# SCH_usbc_module_2022-02-18.net
KiCad netlist of a schematic drawn in EasyEDA
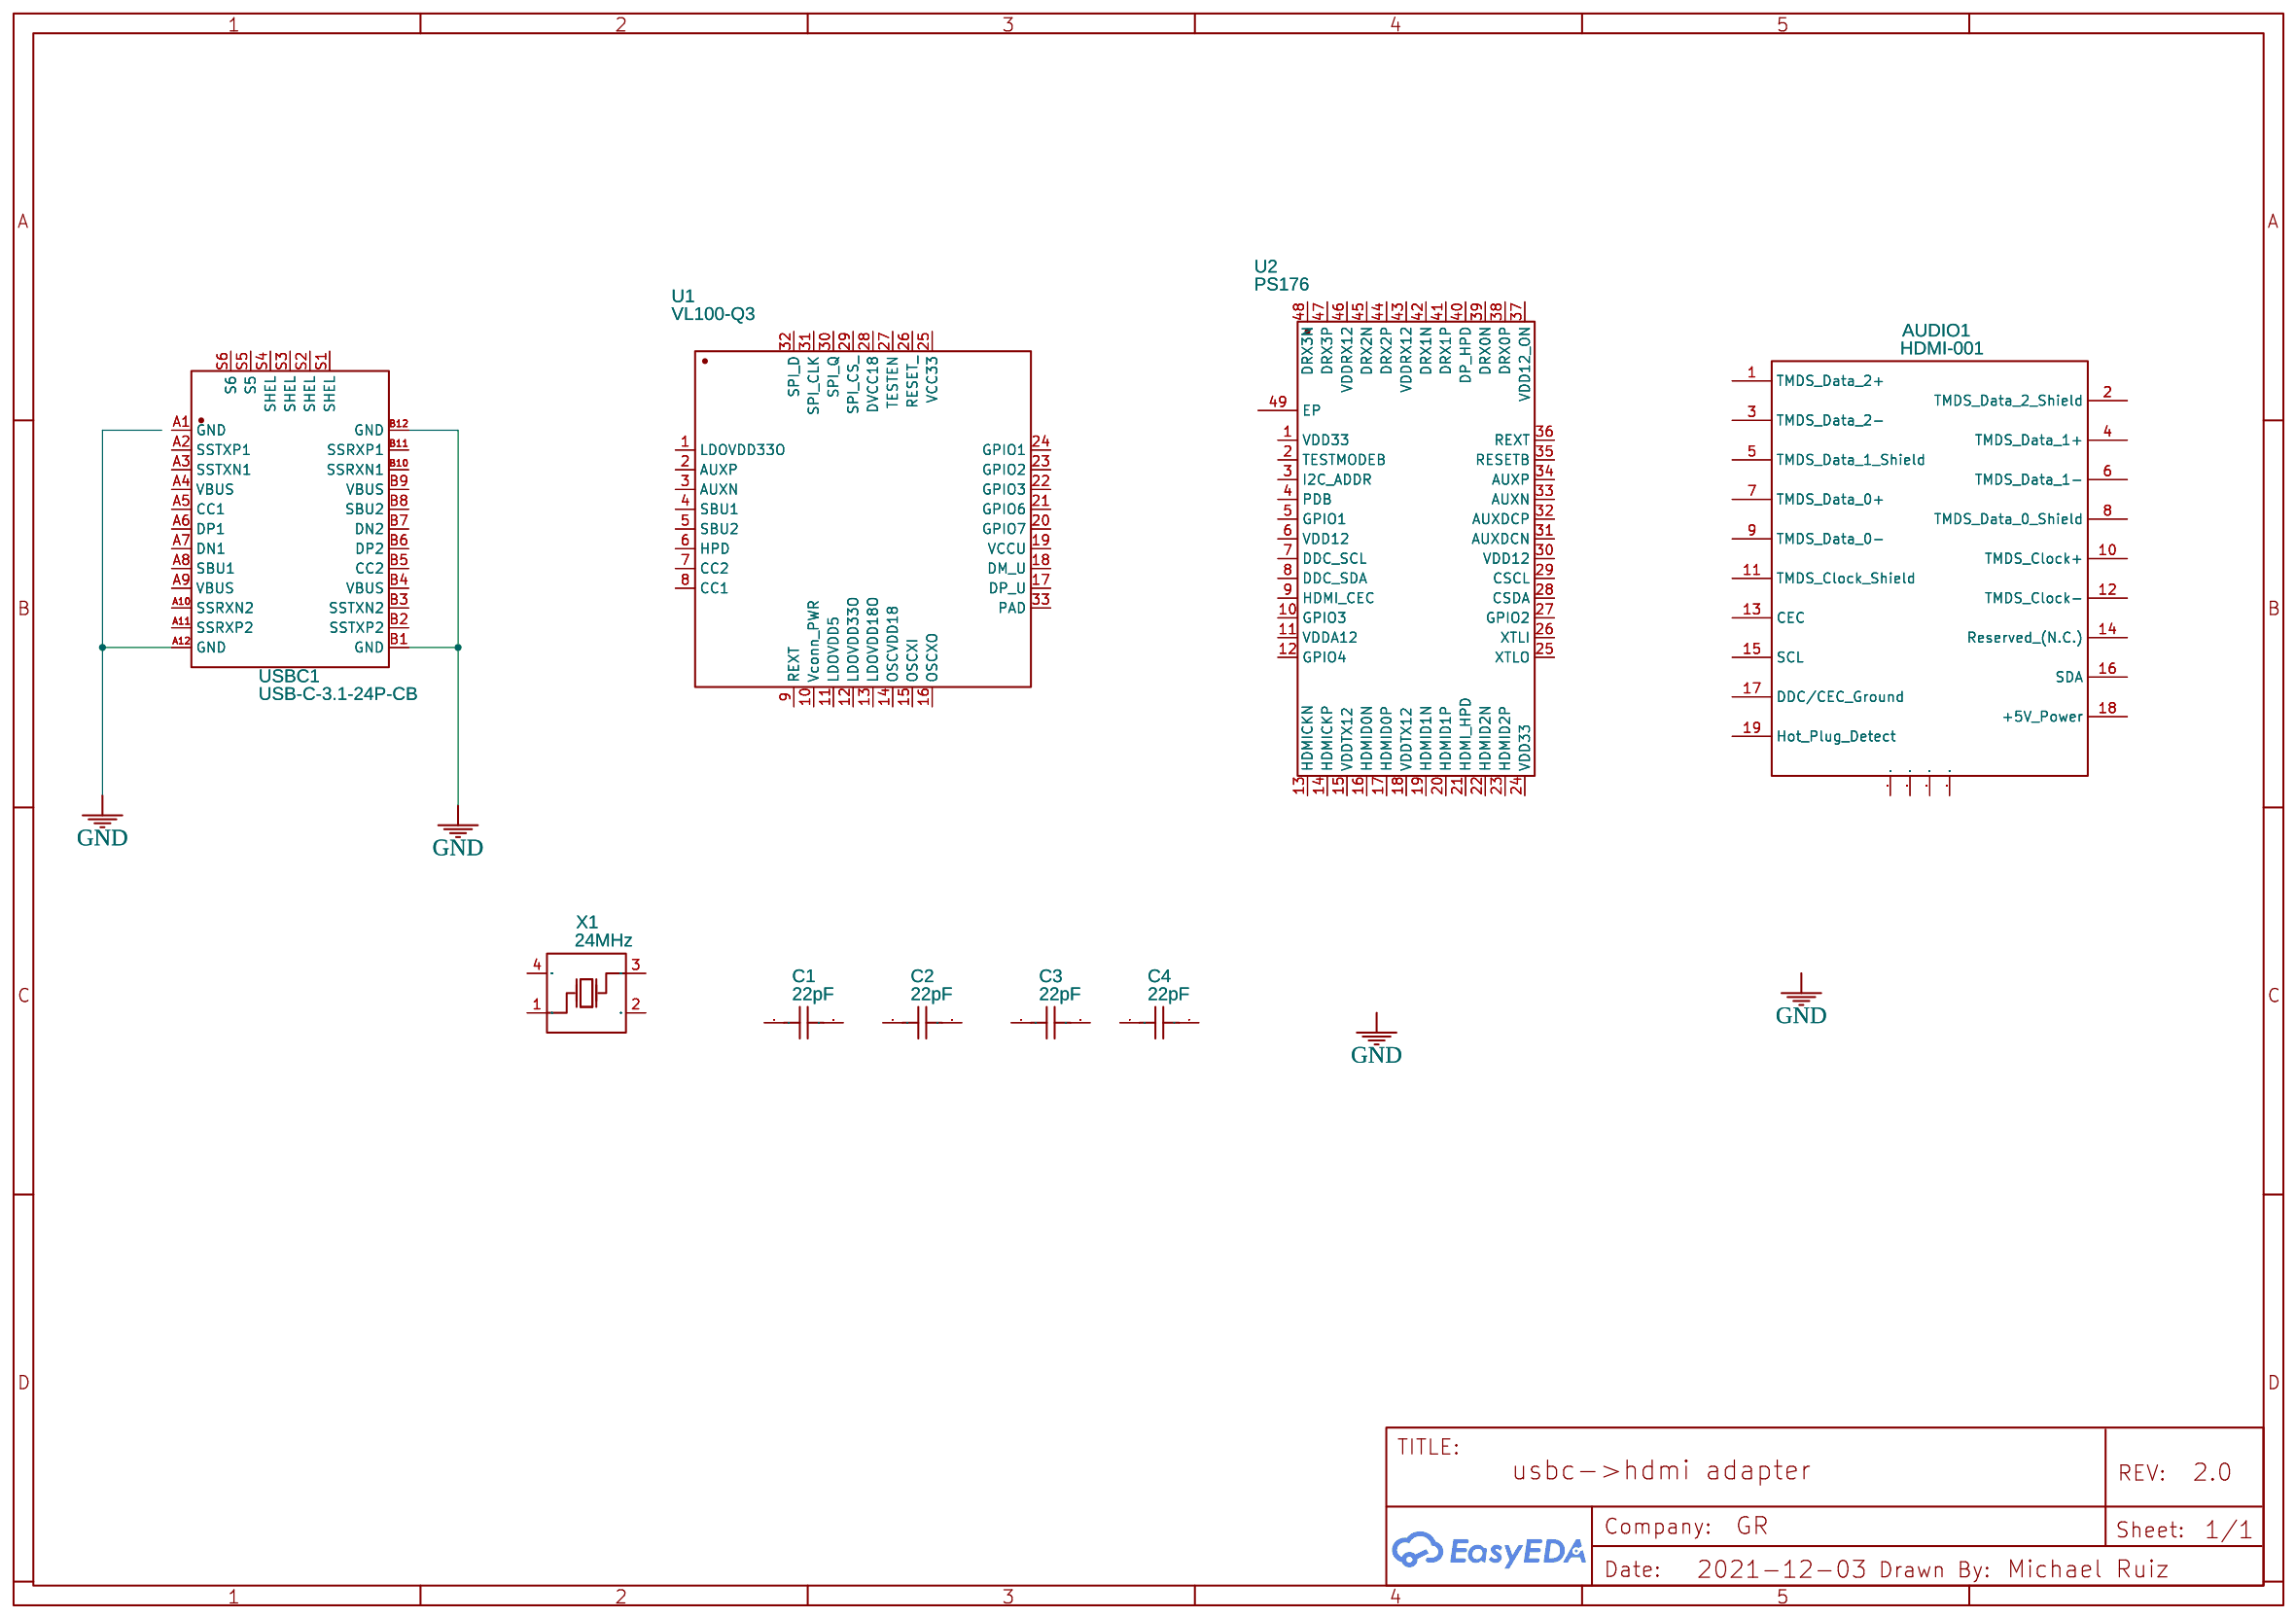
[diagram p0: schematic sheet]

(export (version "E")
  (design (tool "Eeschema 10.0.6"))
  (components
    (comp (ref "AUDIO1")
      (value "HDMI-001")
      (fields (field (name "BOM_Supplier Part") "C138388"))
      (libsource (lib "") (part "HDMI-001"))
    )
    (comp (ref "C1")
      (value "22pF")
      (fields
        (field (name "BOM_Manufacturer Part") "0603N220J500CT")
        (field (name "BOM_Supplier Part") "C2875465")
      )
      (libsource (lib "") (part "0603N220J500CT_C2875465"))
    )
    (comp (ref "C2")
      (value "22pF")
      (fields
        (field (name "BOM_Manufacturer Part") "0603N220J500CT")
        (field (name "BOM_Supplier Part") "C2875465")
      )
      (libsource (lib "") (part "0603N220J500CT_C2875465"))
    )
    (comp (ref "C3")
      (value "22pF")
      (fields
        (field (name "BOM_Manufacturer Part") "0603N220J500CT")
        (field (name "BOM_Supplier Part") "C2875465")
      )
      (libsource (lib "") (part "0603N220J500CT_C2875465"))
    )
    (comp (ref "C4")
      (value "22pF")
      (fields
        (field (name "BOM_Manufacturer Part") "0603N220J500CT")
        (field (name "BOM_Supplier Part") "C2875465")
      )
      (libsource (lib "") (part "0603N220J500CT_C2875465"))
    )
    (comp (ref "U1")
      (value "VL100-Q3")
      (fields (field (name "BOM_Supplier Part") "C69731"))
      (libsource (lib "") (part "VL100-Q3"))
    )
    (comp (ref "U2")
      (value "PS176")
      (fields (field (name "BOM_Supplier Part") "C209703"))
      (libsource (lib "") (part "PS176"))
    )
    (comp (ref "USBC1")
      (value "USB-C-3.1-24P-CB")
      (fields (field (name "BOM_Supplier Part") "C67379"))
      (libsource (lib "") (part "USB-C-3.1-24P-CB"))
    )
    (comp (ref "X1")
      (value "24MHz")
      (fields
        (field (name "BOM_Manufacturer Part") "S2224000091060")
        (field (name "BOM_Supplier Part") "C479185")
      )
      (libsource (lib "") (part "S2224000091060"))
    )
  )
  (nets
    (net (code "1") (name "GND") (class "Default")
      (node (ref "USBC1") (pin "A12") (pinfunction "GND_A12") (pintype "unspecified"))
      (node (ref "USBC1") (pin "B1") (pinfunction "GND_B1") (pintype "unspecified"))
      (node (ref "USBC1") (pin "B12") (pinfunction "GND_B12") (pintype "unspecified"))
    )
    (net (code "2") (name "unconnected-(AUDIO1-+5V_Power-Pad18)") (class "Default")
      (node (ref "AUDIO1") (pin "18") (pinfunction "+5V_Power_18") (pintype "unspecified"))
    )
    (net (code "3") (name "unconnected-(AUDIO1-CEC-Pad13)") (class "Default")
      (node (ref "AUDIO1") (pin "13") (pinfunction "CEC_13") (pintype "unspecified"))
    )
    (net (code "4") (name "unconnected-(AUDIO1-DDC{slash}CEC_Ground-Pad17)") (class "Default")
      (node (ref "AUDIO1") (pin "17") (pinfunction "DDC/CEC_Ground_17") (pintype "unspecified"))
    )
    (net (code "5") (name "unconnected-(AUDIO1-Hot_Plug_Detect-Pad19)") (class "Default")
      (node (ref "AUDIO1") (pin "19") (pinfunction "Hot_Plug_Detect_19") (pintype "unspecified"))
    )
    (net (code "6") (name "unconnected-(AUDIO1-Pad20)") (class "Default")
      (node (ref "AUDIO1") (pin "20") (pinfunction "20_20") (pintype "unspecified"))
    )
    (net (code "7") (name "unconnected-(AUDIO1-Pad21)") (class "Default")
      (node (ref "AUDIO1") (pin "21") (pinfunction "21_21") (pintype "unspecified"))
    )
    (net (code "8") (name "unconnected-(AUDIO1-Pad22)") (class "Default")
      (node (ref "AUDIO1") (pin "22") (pinfunction "22_22") (pintype "unspecified"))
    )
    (net (code "9") (name "unconnected-(AUDIO1-Pad23)") (class "Default")
      (node (ref "AUDIO1") (pin "23") (pinfunction "23_23") (pintype "unspecified"))
    )
    (net (code "10") (name "unconnected-(AUDIO1-Reserved_(N.C.)-Pad14)") (class "Default")
      (node (ref "AUDIO1") (pin "14") (pinfunction "Reserved_(N.C.)_14") (pintype "unspecified"))
    )
    (net (code "11") (name "unconnected-(AUDIO1-SCL-Pad15)") (class "Default")
      (node (ref "AUDIO1") (pin "15") (pinfunction "SCL_15") (pintype "unspecified"))
    )
    (net (code "12") (name "unconnected-(AUDIO1-SDA-Pad16)") (class "Default")
      (node (ref "AUDIO1") (pin "16") (pinfunction "SDA_16") (pintype "unspecified"))
    )
    (net (code "13") (name "unconnected-(AUDIO1-TMDS_Clock+-Pad10)") (class "Default")
      (node (ref "AUDIO1") (pin "10") (pinfunction "TMDS_Clock+_10") (pintype "unspecified"))
    )
    (net (code "14") (name "unconnected-(AUDIO1-TMDS_Clock--Pad12)") (class "Default")
      (node (ref "AUDIO1") (pin "12") (pinfunction "TMDS_Clock-_12") (pintype "unspecified"))
    )
    (net (code "15") (name "unconnected-(AUDIO1-TMDS_Clock_Shield-Pad11)") (class "Default")
      (node (ref "AUDIO1") (pin "11") (pinfunction "TMDS_Clock_Shield_11") (pintype "unspecified"))
    )
    (net (code "16") (name "unconnected-(AUDIO1-TMDS_Data_0+-Pad7)") (class "Default")
      (node (ref "AUDIO1") (pin "7") (pinfunction "TMDS_Data_0+_7") (pintype "unspecified"))
    )
    (net (code "17") (name "unconnected-(AUDIO1-TMDS_Data_0--Pad9)") (class "Default")
      (node (ref "AUDIO1") (pin "9") (pinfunction "TMDS_Data_0-_9") (pintype "unspecified"))
    )
    (net (code "18") (name "unconnected-(AUDIO1-TMDS_Data_0_Shield-Pad8)") (class "Default")
      (node (ref "AUDIO1") (pin "8") (pinfunction "TMDS_Data_0_Shield_8") (pintype "unspecified"))
    )
    (net (code "19") (name "unconnected-(AUDIO1-TMDS_Data_1+-Pad4)") (class "Default")
      (node (ref "AUDIO1") (pin "4") (pinfunction "TMDS_Data_1+_4") (pintype "unspecified"))
    )
    (net (code "20") (name "unconnected-(AUDIO1-TMDS_Data_1--Pad6)") (class "Default")
      (node (ref "AUDIO1") (pin "6") (pinfunction "TMDS_Data_1-_6") (pintype "unspecified"))
    )
    (net (code "21") (name "unconnected-(AUDIO1-TMDS_Data_1_Shield-Pad5)") (class "Default")
      (node (ref "AUDIO1") (pin "5") (pinfunction "TMDS_Data_1_Shield_5") (pintype "unspecified"))
    )
    (net (code "22") (name "unconnected-(AUDIO1-TMDS_Data_2+-Pad1)") (class "Default")
      (node (ref "AUDIO1") (pin "1") (pinfunction "TMDS_Data_2+_1") (pintype "unspecified"))
    )
    (net (code "23") (name "unconnected-(AUDIO1-TMDS_Data_2--Pad3)") (class "Default")
      (node (ref "AUDIO1") (pin "3") (pinfunction "TMDS_Data_2-_3") (pintype "unspecified"))
    )
    (net (code "24") (name "unconnected-(AUDIO1-TMDS_Data_2_Shield-Pad2)") (class "Default")
      (node (ref "AUDIO1") (pin "2") (pinfunction "TMDS_Data_2_Shield_2") (pintype "unspecified"))
    )
    (net (code "25") (name "unconnected-(C1-Pad1)") (class "Default")
      (node (ref "C1") (pin "1") (pinfunction "1_1") (pintype "unspecified"))
    )
    (net (code "26") (name "unconnected-(C1-Pad2)") (class "Default")
      (node (ref "C1") (pin "2") (pinfunction "2_2") (pintype "unspecified"))
    )
    (net (code "27") (name "unconnected-(C2-Pad1)") (class "Default")
      (node (ref "C2") (pin "1") (pinfunction "1_1") (pintype "unspecified"))
    )
    (net (code "28") (name "unconnected-(C2-Pad2)") (class "Default")
      (node (ref "C2") (pin "2") (pinfunction "2_2") (pintype "unspecified"))
    )
    (net (code "29") (name "unconnected-(C3-Pad1)") (class "Default")
      (node (ref "C3") (pin "1") (pinfunction "1_1") (pintype "unspecified"))
    )
    (net (code "30") (name "unconnected-(C3-Pad2)") (class "Default")
      (node (ref "C3") (pin "2") (pinfunction "2_2") (pintype "unspecified"))
    )
    (net (code "31") (name "unconnected-(C4-Pad1)") (class "Default")
      (node (ref "C4") (pin "1") (pinfunction "1_1") (pintype "unspecified"))
    )
    (net (code "32") (name "unconnected-(C4-Pad2)") (class "Default")
      (node (ref "C4") (pin "2") (pinfunction "2_2") (pintype "unspecified"))
    )
    (net (code "33") (name "unconnected-(U1-AUXN-Pad3)") (class "Default")
      (node (ref "U1") (pin "3") (pinfunction "AUXN_3") (pintype "unspecified"))
    )
    (net (code "34") (name "unconnected-(U1-AUXP-Pad2)") (class "Default")
      (node (ref "U1") (pin "2") (pinfunction "AUXP_2") (pintype "unspecified"))
    )
    (net (code "35") (name "unconnected-(U1-CC1-Pad8)") (class "Default")
      (node (ref "U1") (pin "8") (pinfunction "CC1_8") (pintype "unspecified"))
    )
    (net (code "36") (name "unconnected-(U1-CC2-Pad7)") (class "Default")
      (node (ref "U1") (pin "7") (pinfunction "CC2_7") (pintype "unspecified"))
    )
    (net (code "37") (name "unconnected-(U1-DM_U-Pad18)") (class "Default")
      (node (ref "U1") (pin "18") (pinfunction "DM_U_18") (pintype "unspecified"))
    )
    (net (code "38") (name "unconnected-(U1-DP_U-Pad17)") (class "Default")
      (node (ref "U1") (pin "17") (pinfunction "DP_U_17") (pintype "unspecified"))
    )
    (net (code "39") (name "unconnected-(U1-DVCC18-Pad28)") (class "Default")
      (node (ref "U1") (pin "28") (pinfunction "DVCC18_28") (pintype "unspecified"))
    )
    (net (code "40") (name "unconnected-(U1-GPIO1-Pad24)") (class "Default")
      (node (ref "U1") (pin "24") (pinfunction "GPIO1_24") (pintype "unspecified"))
    )
    (net (code "41") (name "unconnected-(U1-GPIO2-Pad23)") (class "Default")
      (node (ref "U1") (pin "23") (pinfunction "GPIO2_23") (pintype "unspecified"))
    )
    (net (code "42") (name "unconnected-(U1-GPIO3-Pad22)") (class "Default")
      (node (ref "U1") (pin "22") (pinfunction "GPIO3_22") (pintype "unspecified"))
    )
    (net (code "43") (name "unconnected-(U1-GPIO6-Pad21)") (class "Default")
      (node (ref "U1") (pin "21") (pinfunction "GPIO6_21") (pintype "unspecified"))
    )
    (net (code "44") (name "unconnected-(U1-GPIO7-Pad20)") (class "Default")
      (node (ref "U1") (pin "20") (pinfunction "GPIO7_20") (pintype "unspecified"))
    )
    (net (code "45") (name "unconnected-(U1-HPD-Pad6)") (class "Default")
      (node (ref "U1") (pin "6") (pinfunction "HPD_6") (pintype "unspecified"))
    )
    (net (code "46") (name "unconnected-(U1-LDOVDD5-Pad11)") (class "Default")
      (node (ref "U1") (pin "11") (pinfunction "LDOVDD5_11") (pintype "unspecified"))
    )
    (net (code "47") (name "unconnected-(U1-LDOVDD18O-Pad13)") (class "Default")
      (node (ref "U1") (pin "13") (pinfunction "LDOVDD18O_13") (pintype "unspecified"))
    )
    (net (code "48") (name "unconnected-(U1-LDOVDD33O-Pad1)") (class "Default")
      (node (ref "U1") (pin "1") (pinfunction "LDOVDD33O_1") (pintype "unspecified"))
    )
    (net (code "49") (name "unconnected-(U1-LDOVDD33O-Pad12)") (class "Default")
      (node (ref "U1") (pin "12") (pinfunction "LDOVDD33O_12") (pintype "unspecified"))
    )
    (net (code "50") (name "unconnected-(U1-OSCVDD18-Pad14)") (class "Default")
      (node (ref "U1") (pin "14") (pinfunction "OSCVDD18_14") (pintype "unspecified"))
    )
    (net (code "51") (name "unconnected-(U1-OSCXI-Pad15)") (class "Default")
      (node (ref "U1") (pin "15") (pinfunction "OSCXI_15") (pintype "unspecified"))
    )
    (net (code "52") (name "unconnected-(U1-OSCXO-Pad16)") (class "Default")
      (node (ref "U1") (pin "16") (pinfunction "OSCXO_16") (pintype "unspecified"))
    )
    (net (code "53") (name "unconnected-(U1-PAD-Pad33)") (class "Default")
      (node (ref "U1") (pin "33") (pinfunction "PAD_33") (pintype "unspecified"))
    )
    (net (code "54") (name "unconnected-(U1-RESET_-Pad26)") (class "Default")
      (node (ref "U1") (pin "26") (pinfunction "RESET__26") (pintype "unspecified"))
    )
    (net (code "55") (name "unconnected-(U1-REXT-Pad9)") (class "Default")
      (node (ref "U1") (pin "9") (pinfunction "REXT_9") (pintype "unspecified"))
    )
    (net (code "56") (name "unconnected-(U1-SBU1-Pad4)") (class "Default")
      (node (ref "U1") (pin "4") (pinfunction "SBU1_4") (pintype "unspecified"))
    )
    (net (code "57") (name "unconnected-(U1-SBU2-Pad5)") (class "Default")
      (node (ref "U1") (pin "5") (pinfunction "SBU2_5") (pintype "unspecified"))
    )
    (net (code "58") (name "unconnected-(U1-SPI_CLK-Pad31)") (class "Default")
      (node (ref "U1") (pin "31") (pinfunction "SPI_CLK_31") (pintype "unspecified"))
    )
    (net (code "59") (name "unconnected-(U1-SPI_CS_-Pad29)") (class "Default")
      (node (ref "U1") (pin "29") (pinfunction "SPI_CS__29") (pintype "unspecified"))
    )
    (net (code "60") (name "unconnected-(U1-SPI_D-Pad32)") (class "Default")
      (node (ref "U1") (pin "32") (pinfunction "SPI_D_32") (pintype "unspecified"))
    )
    (net (code "61") (name "unconnected-(U1-SPI_Q-Pad30)") (class "Default")
      (node (ref "U1") (pin "30") (pinfunction "SPI_Q_30") (pintype "unspecified"))
    )
    (net (code "62") (name "unconnected-(U1-TESTEN-Pad27)") (class "Default")
      (node (ref "U1") (pin "27") (pinfunction "TESTEN_27") (pintype "unspecified"))
    )
    (net (code "63") (name "unconnected-(U1-VCC33-Pad25)") (class "Default")
      (node (ref "U1") (pin "25") (pinfunction "VCC33_25") (pintype "unspecified"))
    )
    (net (code "64") (name "unconnected-(U1-VCCU-Pad19)") (class "Default")
      (node (ref "U1") (pin "19") (pinfunction "VCCU_19") (pintype "unspecified"))
    )
    (net (code "65") (name "unconnected-(U1-Vconn_PWR-Pad10)") (class "Default")
      (node (ref "U1") (pin "10") (pinfunction "Vconn_PWR_10") (pintype "unspecified"))
    )
    (net (code "66") (name "unconnected-(U2-AUXDCN-Pad31)") (class "Default")
      (node (ref "U2") (pin "31") (pinfunction "AUXDCN_31") (pintype "unspecified"))
    )
    (net (code "67") (name "unconnected-(U2-AUXDCP-Pad32)") (class "Default")
      (node (ref "U2") (pin "32") (pinfunction "AUXDCP_32") (pintype "unspecified"))
    )
    (net (code "68") (name "unconnected-(U2-AUXN-Pad33)") (class "Default")
      (node (ref "U2") (pin "33") (pinfunction "AUXN_33") (pintype "unspecified"))
    )
    (net (code "69") (name "unconnected-(U2-AUXP-Pad34)") (class "Default")
      (node (ref "U2") (pin "34") (pinfunction "AUXP_34") (pintype "unspecified"))
    )
    (net (code "70") (name "unconnected-(U2-CSCL-Pad29)") (class "Default")
      (node (ref "U2") (pin "29") (pinfunction "CSCL_29") (pintype "unspecified"))
    )
    (net (code "71") (name "unconnected-(U2-CSDA-Pad28)") (class "Default")
      (node (ref "U2") (pin "28") (pinfunction "CSDA_28") (pintype "unspecified"))
    )
    (net (code "72") (name "unconnected-(U2-DDC_SCL-Pad7)") (class "Default")
      (node (ref "U2") (pin "7") (pinfunction "DDC_SCL_7") (pintype "unspecified"))
    )
    (net (code "73") (name "unconnected-(U2-DDC_SDA-Pad8)") (class "Default")
      (node (ref "U2") (pin "8") (pinfunction "DDC_SDA_8") (pintype "unspecified"))
    )
    (net (code "74") (name "unconnected-(U2-DP_HPD-Pad40)") (class "Default")
      (node (ref "U2") (pin "40") (pinfunction "DP_HPD_40") (pintype "unspecified"))
    )
    (net (code "75") (name "unconnected-(U2-DRX0N-Pad39)") (class "Default")
      (node (ref "U2") (pin "39") (pinfunction "DRX0N_39") (pintype "unspecified"))
    )
    (net (code "76") (name "unconnected-(U2-DRX0P-Pad38)") (class "Default")
      (node (ref "U2") (pin "38") (pinfunction "DRX0P_38") (pintype "unspecified"))
    )
    (net (code "77") (name "unconnected-(U2-DRX1N-Pad42)") (class "Default")
      (node (ref "U2") (pin "42") (pinfunction "DRX1N_42") (pintype "unspecified"))
    )
    (net (code "78") (name "unconnected-(U2-DRX1P-Pad41)") (class "Default")
      (node (ref "U2") (pin "41") (pinfunction "DRX1P_41") (pintype "unspecified"))
    )
    (net (code "79") (name "unconnected-(U2-DRX2N-Pad45)") (class "Default")
      (node (ref "U2") (pin "45") (pinfunction "DRX2N_45") (pintype "unspecified"))
    )
    (net (code "80") (name "unconnected-(U2-DRX2P-Pad44)") (class "Default")
      (node (ref "U2") (pin "44") (pinfunction "DRX2P_44") (pintype "unspecified"))
    )
    (net (code "81") (name "unconnected-(U2-DRX3N-Pad48)") (class "Default")
      (node (ref "U2") (pin "48") (pinfunction "DRX3N_48") (pintype "unspecified"))
    )
    (net (code "82") (name "unconnected-(U2-DRX3P-Pad47)") (class "Default")
      (node (ref "U2") (pin "47") (pinfunction "DRX3P_47") (pintype "unspecified"))
    )
    (net (code "83") (name "unconnected-(U2-EP-Pad49)") (class "Default")
      (node (ref "U2") (pin "49") (pinfunction "EP_49") (pintype "unspecified"))
    )
    (net (code "84") (name "unconnected-(U2-GPIO1-Pad5)") (class "Default")
      (node (ref "U2") (pin "5") (pinfunction "GPIO1_5") (pintype "unspecified"))
    )
    (net (code "85") (name "unconnected-(U2-GPIO2-Pad27)") (class "Default")
      (node (ref "U2") (pin "27") (pinfunction "GPIO2_27") (pintype "unspecified"))
    )
    (net (code "86") (name "unconnected-(U2-GPIO3-Pad10)") (class "Default")
      (node (ref "U2") (pin "10") (pinfunction "GPIO3_10") (pintype "unspecified"))
    )
    (net (code "87") (name "unconnected-(U2-GPIO4-Pad12)") (class "Default")
      (node (ref "U2") (pin "12") (pinfunction "GPIO4_12") (pintype "unspecified"))
    )
    (net (code "88") (name "unconnected-(U2-HDMICKN-Pad13)") (class "Default")
      (node (ref "U2") (pin "13") (pinfunction "HDMICKN_13") (pintype "unspecified"))
    )
    (net (code "89") (name "unconnected-(U2-HDMICKP-Pad14)") (class "Default")
      (node (ref "U2") (pin "14") (pinfunction "HDMICKP_14") (pintype "unspecified"))
    )
    (net (code "90") (name "unconnected-(U2-HDMID0N-Pad16)") (class "Default")
      (node (ref "U2") (pin "16") (pinfunction "HDMID0N_16") (pintype "unspecified"))
    )
    (net (code "91") (name "unconnected-(U2-HDMID0P-Pad17)") (class "Default")
      (node (ref "U2") (pin "17") (pinfunction "HDMID0P_17") (pintype "unspecified"))
    )
    (net (code "92") (name "unconnected-(U2-HDMID1N-Pad19)") (class "Default")
      (node (ref "U2") (pin "19") (pinfunction "HDMID1N_19") (pintype "unspecified"))
    )
    (net (code "93") (name "unconnected-(U2-HDMID1P-Pad20)") (class "Default")
      (node (ref "U2") (pin "20") (pinfunction "HDMID1P_20") (pintype "unspecified"))
    )
    (net (code "94") (name "unconnected-(U2-HDMID2N-Pad22)") (class "Default")
      (node (ref "U2") (pin "22") (pinfunction "HDMID2N_22") (pintype "unspecified"))
    )
    (net (code "95") (name "unconnected-(U2-HDMID2P-Pad23)") (class "Default")
      (node (ref "U2") (pin "23") (pinfunction "HDMID2P_23") (pintype "unspecified"))
    )
    (net (code "96") (name "unconnected-(U2-HDMI_CEC-Pad9)") (class "Default")
      (node (ref "U2") (pin "9") (pinfunction "HDMI_CEC_9") (pintype "unspecified"))
    )
    (net (code "97") (name "unconnected-(U2-HDMI_HPD-Pad21)") (class "Default")
      (node (ref "U2") (pin "21") (pinfunction "HDMI_HPD_21") (pintype "unspecified"))
    )
    (net (code "98") (name "unconnected-(U2-I2C_ADDR-Pad3)") (class "Default")
      (node (ref "U2") (pin "3") (pinfunction "I2C_ADDR_3") (pintype "unspecified"))
    )
    (net (code "99") (name "unconnected-(U2-PDB-Pad4)") (class "Default")
      (node (ref "U2") (pin "4") (pinfunction "PDB_4") (pintype "unspecified"))
    )
    (net (code "100") (name "unconnected-(U2-RESETB-Pad35)") (class "Default")
      (node (ref "U2") (pin "35") (pinfunction "RESETB_35") (pintype "unspecified"))
    )
    (net (code "101") (name "unconnected-(U2-REXT-Pad36)") (class "Default")
      (node (ref "U2") (pin "36") (pinfunction "REXT_36") (pintype "unspecified"))
    )
    (net (code "102") (name "unconnected-(U2-TESTMODEB-Pad2)") (class "Default")
      (node (ref "U2") (pin "2") (pinfunction "TESTMODEB_2") (pintype "unspecified"))
    )
    (net (code "103") (name "unconnected-(U2-VDD12-Pad6)") (class "Default")
      (node (ref "U2") (pin "6") (pinfunction "VDD12_6") (pintype "unspecified"))
    )
    (net (code "104") (name "unconnected-(U2-VDD12-Pad30)") (class "Default")
      (node (ref "U2") (pin "30") (pinfunction "VDD12_30") (pintype "unspecified"))
    )
    (net (code "105") (name "unconnected-(U2-VDD12_ON-Pad37)") (class "Default")
      (node (ref "U2") (pin "37") (pinfunction "VDD12_ON_37") (pintype "unspecified"))
    )
    (net (code "106") (name "unconnected-(U2-VDD33-Pad1)") (class "Default")
      (node (ref "U2") (pin "1") (pinfunction "VDD33_1") (pintype "unspecified"))
    )
    (net (code "107") (name "unconnected-(U2-VDD33-Pad24)") (class "Default")
      (node (ref "U2") (pin "24") (pinfunction "VDD33_24") (pintype "unspecified"))
    )
    (net (code "108") (name "unconnected-(U2-VDDA12-Pad11)") (class "Default")
      (node (ref "U2") (pin "11") (pinfunction "VDDA12_11") (pintype "unspecified"))
    )
    (net (code "109") (name "unconnected-(U2-VDDRX12-Pad43)") (class "Default")
      (node (ref "U2") (pin "43") (pinfunction "VDDRX12_43") (pintype "unspecified"))
    )
    (net (code "110") (name "unconnected-(U2-VDDRX12-Pad46)") (class "Default")
      (node (ref "U2") (pin "46") (pinfunction "VDDRX12_46") (pintype "unspecified"))
    )
    (net (code "111") (name "unconnected-(U2-VDDTX12-Pad15)") (class "Default")
      (node (ref "U2") (pin "15") (pinfunction "VDDTX12_15") (pintype "unspecified"))
    )
    (net (code "112") (name "unconnected-(U2-VDDTX12-Pad18)") (class "Default")
      (node (ref "U2") (pin "18") (pinfunction "VDDTX12_18") (pintype "unspecified"))
    )
    (net (code "113") (name "unconnected-(U2-XTLI-Pad26)") (class "Default")
      (node (ref "U2") (pin "26") (pinfunction "XTLI_26") (pintype "unspecified"))
    )
    (net (code "114") (name "unconnected-(U2-XTLO-Pad25)") (class "Default")
      (node (ref "U2") (pin "25") (pinfunction "XTLO_25") (pintype "unspecified"))
    )
    (net (code "115") (name "unconnected-(USBC1-CC1-PadA5)") (class "Default")
      (node (ref "USBC1") (pin "A5") (pinfunction "CC1_A5") (pintype "unspecified"))
    )
    (net (code "116") (name "unconnected-(USBC1-CC2-PadB5)") (class "Default")
      (node (ref "USBC1") (pin "B5") (pinfunction "CC2_B5") (pintype "unspecified"))
    )
    (net (code "117") (name "unconnected-(USBC1-DN1-PadA7)") (class "Default")
      (node (ref "USBC1") (pin "A7") (pinfunction "DN1_A7") (pintype "unspecified"))
    )
    (net (code "118") (name "unconnected-(USBC1-DN2-PadB7)") (class "Default")
      (node (ref "USBC1") (pin "B7") (pinfunction "DN2_B7") (pintype "unspecified"))
    )
    (net (code "119") (name "unconnected-(USBC1-DP1-PadA6)") (class "Default")
      (node (ref "USBC1") (pin "A6") (pinfunction "DP1_A6") (pintype "unspecified"))
    )
    (net (code "120") (name "unconnected-(USBC1-DP2-PadB6)") (class "Default")
      (node (ref "USBC1") (pin "B6") (pinfunction "DP2_B6") (pintype "unspecified"))
    )
    (net (code "121") (name "unconnected-(USBC1-GND-PadA1)") (class "Default")
      (node (ref "USBC1") (pin "A1") (pinfunction "GND_A1") (pintype "unspecified"))
    )
    (net (code "122") (name "unconnected-(USBC1-PadS5)") (class "Default")
      (node (ref "USBC1") (pin "S5") (pinfunction "S5_S5") (pintype "unspecified"))
    )
    (net (code "123") (name "unconnected-(USBC1-PadS6)") (class "Default")
      (node (ref "USBC1") (pin "S6") (pinfunction "S6_S6") (pintype "unspecified"))
    )
    (net (code "124") (name "unconnected-(USBC1-SBU1-PadA8)") (class "Default")
      (node (ref "USBC1") (pin "A8") (pinfunction "SBU1_A8") (pintype "unspecified"))
    )
    (net (code "125") (name "unconnected-(USBC1-SBU2-PadB8)") (class "Default")
      (node (ref "USBC1") (pin "B8") (pinfunction "SBU2_B8") (pintype "unspecified"))
    )
    (net (code "126") (name "unconnected-(USBC1-SHEL-PadS1)") (class "Default")
      (node (ref "USBC1") (pin "S1") (pinfunction "SHEL_S1") (pintype "unspecified"))
    )
    (net (code "127") (name "unconnected-(USBC1-SHEL-PadS2)") (class "Default")
      (node (ref "USBC1") (pin "S2") (pinfunction "SHEL_S2") (pintype "unspecified"))
    )
    (net (code "128") (name "unconnected-(USBC1-SHEL-PadS3)") (class "Default")
      (node (ref "USBC1") (pin "S3") (pinfunction "SHEL_S3") (pintype "unspecified"))
    )
    (net (code "129") (name "unconnected-(USBC1-SHEL-PadS4)") (class "Default")
      (node (ref "USBC1") (pin "S4") (pinfunction "SHEL_S4") (pintype "unspecified"))
    )
    (net (code "130") (name "unconnected-(USBC1-SSRXN1-PadB10)") (class "Default")
      (node (ref "USBC1") (pin "B10") (pinfunction "SSRXN1_B10") (pintype "unspecified"))
    )
    (net (code "131") (name "unconnected-(USBC1-SSRXN2-PadA10)") (class "Default")
      (node (ref "USBC1") (pin "A10") (pinfunction "SSRXN2_A10") (pintype "unspecified"))
    )
    (net (code "132") (name "unconnected-(USBC1-SSRXP1-PadB11)") (class "Default")
      (node (ref "USBC1") (pin "B11") (pinfunction "SSRXP1_B11") (pintype "unspecified"))
    )
    (net (code "133") (name "unconnected-(USBC1-SSRXP2-PadA11)") (class "Default")
      (node (ref "USBC1") (pin "A11") (pinfunction "SSRXP2_A11") (pintype "unspecified"))
    )
    (net (code "134") (name "unconnected-(USBC1-SSTXN1-PadA3)") (class "Default")
      (node (ref "USBC1") (pin "A3") (pinfunction "SSTXN1_A3") (pintype "unspecified"))
    )
    (net (code "135") (name "unconnected-(USBC1-SSTXN2-PadB3)") (class "Default")
      (node (ref "USBC1") (pin "B3") (pinfunction "SSTXN2_B3") (pintype "unspecified"))
    )
    (net (code "136") (name "unconnected-(USBC1-SSTXP1-PadA2)") (class "Default")
      (node (ref "USBC1") (pin "A2") (pinfunction "SSTXP1_A2") (pintype "unspecified"))
    )
    (net (code "137") (name "unconnected-(USBC1-SSTXP2-PadB2)") (class "Default")
      (node (ref "USBC1") (pin "B2") (pinfunction "SSTXP2_B2") (pintype "unspecified"))
    )
    (net (code "138") (name "unconnected-(USBC1-VBUS-PadA4)") (class "Default")
      (node (ref "USBC1") (pin "A4") (pinfunction "VBUS_A4") (pintype "unspecified"))
    )
    (net (code "139") (name "unconnected-(USBC1-VBUS-PadA9)") (class "Default")
      (node (ref "USBC1") (pin "A9") (pinfunction "VBUS_A9") (pintype "unspecified"))
    )
    (net (code "140") (name "unconnected-(USBC1-VBUS-PadB4)") (class "Default")
      (node (ref "USBC1") (pin "B4") (pinfunction "VBUS_B4") (pintype "unspecified"))
    )
    (net (code "141") (name "unconnected-(USBC1-VBUS-PadB9)") (class "Default")
      (node (ref "USBC1") (pin "B9") (pinfunction "VBUS_B9") (pintype "unspecified"))
    )
    (net (code "142") (name "unconnected-(X1-GND-Pad2)") (class "Default")
      (node (ref "X1") (pin "2") (pinfunction "GND_2") (pintype "unspecified"))
    )
    (net (code "143") (name "unconnected-(X1-GND-Pad4)") (class "Default")
      (node (ref "X1") (pin "4") (pinfunction "GND_4") (pintype "unspecified"))
    )
    (net (code "144") (name "unconnected-(X1-OSC1-Pad1)") (class "Default")
      (node (ref "X1") (pin "1") (pinfunction "OSC1_1") (pintype "unspecified"))
    )
    (net (code "145") (name "unconnected-(X1-OSC2-Pad3)") (class "Default")
      (node (ref "X1") (pin "3") (pinfunction "OSC2_3") (pintype "unspecified"))
    )
  )
)
